# psvsd-v21.net
KiCad netlist of a schematic drawn in EAGLE
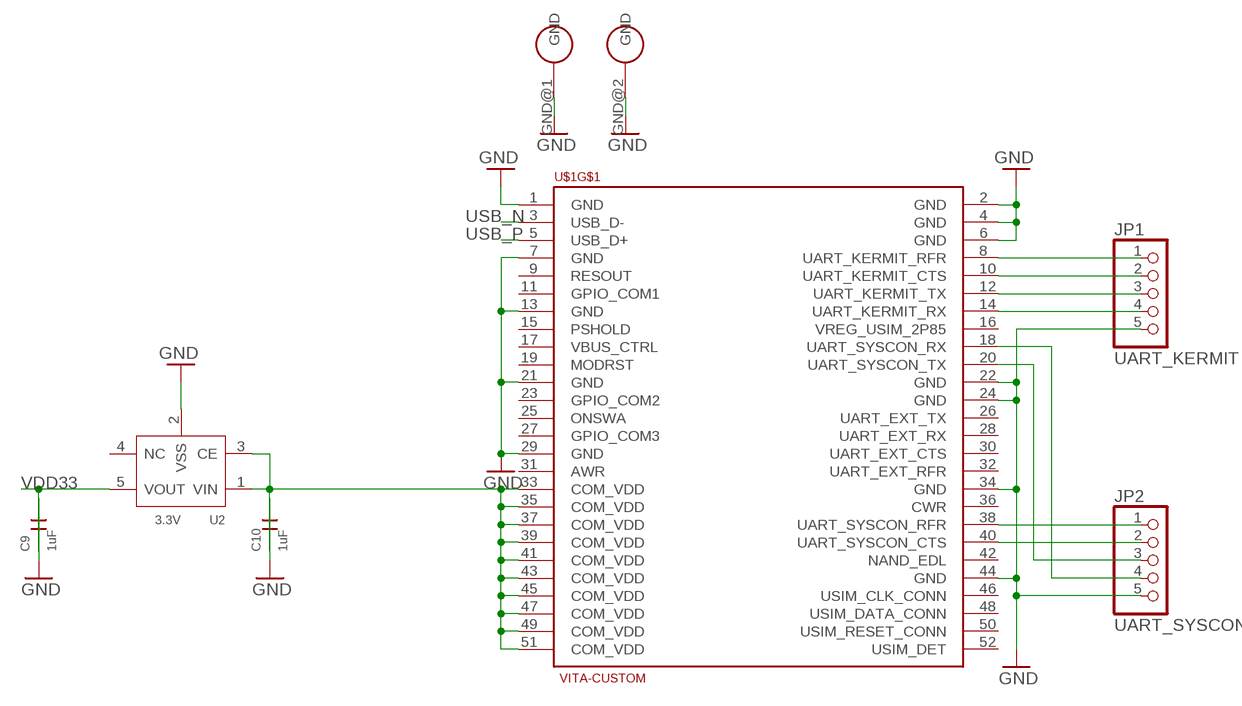
[diagram p0: schematic, sheet 1]
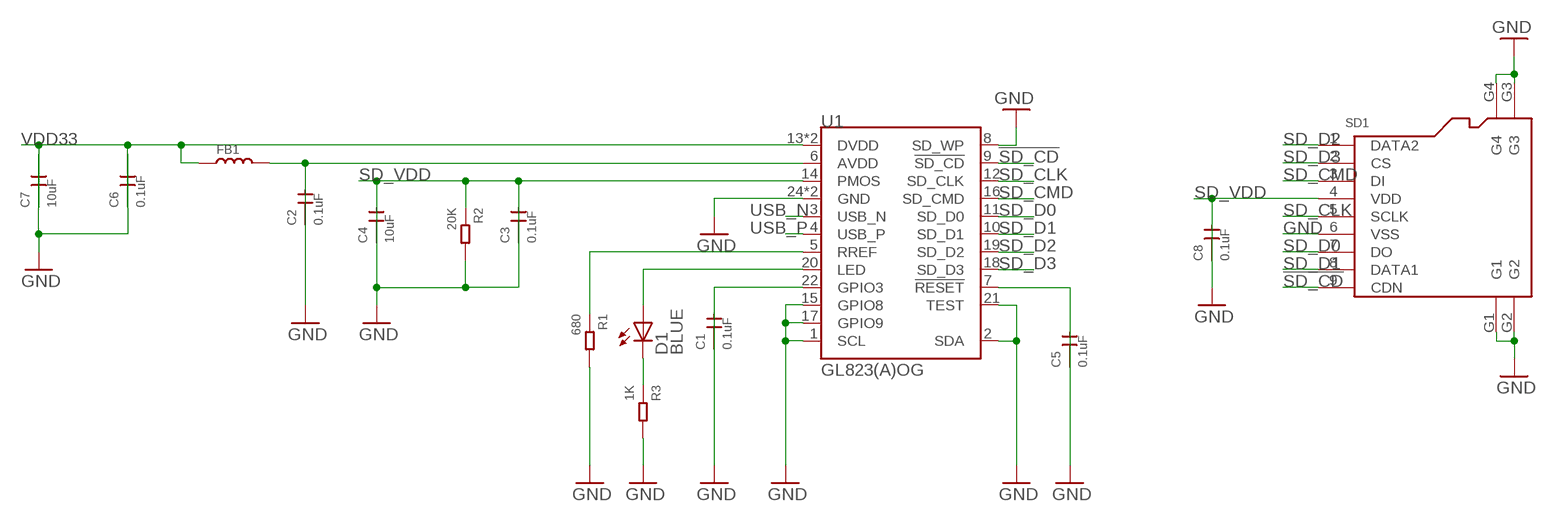
[diagram p1: schematic, sheet 2]

(export (version "E")
  (design (tool "Eeschema 10.0.6"))
  (components
    (comp (ref "C9")
      (value "1uF")
      (footprint "eagle-import:C0603")
      (fields (field (name "MPN") "GRM1885C1H102JA01D"))
      (libsource (lib "eagle-import") (part "CERAMIC-1NF-50V-5%-C0G(0603)"))
    )
    (comp (ref "C10")
      (value "1uF")
      (footprint "eagle-import:C0603")
      (fields (field (name "MPN") "GRM1885C1H102JA01D"))
      (libsource (lib "eagle-import") (part "CERAMIC-1NF-50V-5%-C0G(0603)"))
    )
    (comp (ref "JP1")
      (value "UART_KERMIT")
      (footprint "eagle-import:1X05")
      (libsource (lib "eagle-import") (part "PINHD-1X5"))
    )
    (comp (ref "JP2")
      (value "UART_SYSCON")
      (footprint "eagle-import:1X05")
      (libsource (lib "eagle-import") (part "PINHD-1X5"))
    )
    (comp (ref "U$1")
      (value "VITA-CUSTOM")
      (footprint "eagle-import:VITA-MINI-PCI-E")
      (libsource (lib "eagle-import") (part "VITA-CUSTOM"))
    )
    (comp (ref "U2")
      (value "3.3V")
      (footprint "eagle-import:SOT-23-5")
      (fields (field (name "MPN") "XC6204B332MR"))
      (libsource (lib "eagle-import") (part "PMIC-LDO-XC6204B332MR(SOT23-5)"))
    )
    (comp (ref "C1")
      (value "0.1uF")
      (footprint "eagle-import:C0603")
      (fields (field (name "MPN") "GRM1885C1H102JA01D"))
      (libsource (lib "eagle-import") (part "CERAMIC-1NF-50V-5%-C0G(0603)"))
    )
    (comp (ref "C2")
      (value "0.1uF")
      (footprint "eagle-import:C0603")
      (fields (field (name "MPN") "GRM1885C1H102JA01D"))
      (libsource (lib "eagle-import") (part "CERAMIC-1NF-50V-5%-C0G(0603)"))
    )
    (comp (ref "C3")
      (value "0.1uF")
      (footprint "eagle-import:C0603")
      (fields (field (name "MPN") "GRM1885C1H102JA01D"))
      (libsource (lib "eagle-import") (part "CERAMIC-1NF-50V-5%-C0G(0603)"))
    )
    (comp (ref "C4")
      (value "10uF")
      (footprint "eagle-import:C0603")
      (fields (field (name "MPN") "GRM1885C1H102JA01D"))
      (libsource (lib "eagle-import") (part "CERAMIC-1NF-50V-5%-C0G(0603)"))
    )
    (comp (ref "C5")
      (value "0.1uF")
      (footprint "eagle-import:C0603")
      (fields (field (name "MPN") "GRM1885C1H102JA01D"))
      (libsource (lib "eagle-import") (part "CERAMIC-1NF-50V-5%-C0G(0603)"))
    )
    (comp (ref "C6")
      (value "0.1uF")
      (footprint "eagle-import:C0603")
      (fields (field (name "MPN") "GRM1885C1H102JA01D"))
      (libsource (lib "eagle-import") (part "CERAMIC-1NF-50V-5%-C0G(0603)"))
    )
    (comp (ref "C7")
      (value "10uF")
      (footprint "eagle-import:C0603")
      (fields (field (name "MPN") "GRM1885C1H102JA01D"))
      (libsource (lib "eagle-import") (part "CERAMIC-1NF-50V-5%-C0G(0603)"))
    )
    (comp (ref "C8")
      (value "0.1uF")
      (footprint "eagle-import:C0603")
      (fields (field (name "MPN") "GRM1885C1H102JA01D"))
      (libsource (lib "eagle-import") (part "CERAMIC-1NF-50V-5%-C0G(0603)"))
    )
    (comp (ref "D1")
      (value "BLUE")
      (footprint "eagle-import:CHIP-LED0603")
      (libsource (lib "eagle-import") (part "LEDCHIP-LED0603"))
    )
    (comp (ref "FB1")
      (value "SMD-FERRITE-BEAD-2500R-50MA(0603)")
      (footprint "eagle-import:L0603")
      (libsource (lib "eagle-import") (part "SMD-FERRITE-BEAD-2500R-50MA(0603)"))
    )
    (comp (ref "R1")
      (value "680")
      (footprint "eagle-import:R0603")
      (fields (field (name "MPN") "RC0603JR-070RL"))
      (libsource (lib "eagle-import") (part "SMD-RES-0R-5%-1/10W(0603)"))
    )
    (comp (ref "R2")
      (value "20K")
      (footprint "eagle-import:R0603")
      (fields (field (name "MPN") "RC0603JR-070RL"))
      (libsource (lib "eagle-import") (part "SMD-RES-0R-5%-1/10W(0603)"))
    )
    (comp (ref "R3")
      (value "1K")
      (footprint "eagle-import:R0603")
      (fields (field (name "MPN") "RC0603JR-070RL"))
      (libsource (lib "eagle-import") (part "SMD-RES-0R-5%-1/10W(0603)"))
    )
    (comp (ref "SD1")
      (value "MICRO-SD-CARD-SOCKET-9P(ST-TF-003A)")
      (footprint "eagle-import:MICRO-SD9+4P-SMD-16.1X14.5X1.85MM")
      (fields (field (name "MPN") "ST-TF-003A"))
      (libsource (lib "eagle-import") (part "MICRO-SD-CARD-SOCKET-9P(ST-TF-003A)"))
    )
    (comp (ref "U1")
      (value "GL823(A)OG")
      (footprint "eagle-import:QFN-24")
      (libsource (lib "eagle-import") (part "GL823(A)OG"))
    )
  )
  (nets
    (net (code "1") (name "GND") (class "Default")
      (node (ref "C1") (pin "2") (pinfunction "2_2") (pintype "passive"))
      (node (ref "C10") (pin "2") (pinfunction "2_2") (pintype "passive"))
      (node (ref "C2") (pin "2") (pinfunction "2_2") (pintype "passive"))
      (node (ref "C3") (pin "2") (pinfunction "2_2") (pintype "passive"))
      (node (ref "C4") (pin "2") (pinfunction "2_2") (pintype "passive"))
      (node (ref "C5") (pin "2") (pinfunction "2_2") (pintype "passive"))
      (node (ref "C6") (pin "2") (pinfunction "2_2") (pintype "passive"))
      (node (ref "C7") (pin "2") (pinfunction "2_2") (pintype "passive"))
      (node (ref "C8") (pin "2") (pinfunction "2_2") (pintype "passive"))
      (node (ref "C9") (pin "2") (pinfunction "2_2") (pintype "passive"))
      (node (ref "JP1") (pin "5") (pinfunction "5_5") (pintype "passive"))
      (node (ref "JP2") (pin "5") (pinfunction "5_5") (pintype "passive"))
      (node (ref "R1") (pin "2") (pinfunction "2_2") (pintype "passive"))
      (node (ref "R2") (pin "2") (pinfunction "2_2") (pintype "passive"))
      (node (ref "R3") (pin "2") (pinfunction "2_2") (pintype "passive"))
      (node (ref "SD1") (pin "6") (pinfunction "VSS_6") (pintype "bidirectional"))
      (node (ref "SD1") (pin "G1") (pinfunction "G1_G1") (pintype "bidirectional"))
      (node (ref "SD1") (pin "G2") (pinfunction "G2_G2") (pintype "bidirectional"))
      (node (ref "SD1") (pin "G3") (pinfunction "G3_G3") (pintype "bidirectional"))
      (node (ref "SD1") (pin "G4") (pinfunction "G4_G4") (pintype "bidirectional"))
      (node (ref "U$1") (pin "1") (pinfunction "GND_1") (pintype "bidirectional"))
      (node (ref "U$1") (pin "13") (pinfunction "GND_13") (pintype "bidirectional"))
      (node (ref "U$1") (pin "2") (pinfunction "GND_2") (pintype "bidirectional"))
      (node (ref "U$1") (pin "21") (pinfunction "GND_21") (pintype "bidirectional"))
      (node (ref "U$1") (pin "22") (pinfunction "GND_22") (pintype "bidirectional"))
      (node (ref "U$1") (pin "24") (pinfunction "GND_24") (pintype "bidirectional"))
      (node (ref "U$1") (pin "29") (pinfunction "GND_29") (pintype "bidirectional"))
      (node (ref "U$1") (pin "34") (pinfunction "GND_34") (pintype "bidirectional"))
      (node (ref "U$1") (pin "4") (pinfunction "GND_4") (pintype "bidirectional"))
      (node (ref "U$1") (pin "44") (pinfunction "GND_44") (pintype "bidirectional"))
      (node (ref "U$1") (pin "6") (pinfunction "GND_6") (pintype "bidirectional"))
      (node (ref "U$1") (pin "7") (pinfunction "GND_7") (pintype "bidirectional"))
      (node (ref "U$1") (pin "GND@1") (pinfunction "GND_GND@1") (pintype "power_in"))
      (node (ref "U$1") (pin "GND@2") (pinfunction "GND_GND@2") (pintype "power_in"))
      (node (ref "U1") (pin "1") (pinfunction "SCL_1") (pintype "bidirectional"))
      (node (ref "U1") (pin "15") (pinfunction "GPIO8_15") (pintype "bidirectional"))
      (node (ref "U1") (pin "17") (pinfunction "GPIO9_17") (pintype "bidirectional"))
      (node (ref "U1") (pin "2") (pinfunction "SDA_2") (pintype "bidirectional"))
      (node (ref "U1") (pin "21") (pinfunction "TEST_21") (pintype "input"))
      (node (ref "U1") (pin "24") (pinfunction "GND_24") (pintype "power_in"))
      (node (ref "U1") (pin "25") (pinfunction "GND_25") (pintype "power_in"))
      (node (ref "U1") (pin "8") (pinfunction "SD_WP_8") (pintype "input"))
      (node (ref "U2") (pin "2") (pinfunction "VSS_2") (pintype "power_in"))
    )
    (net (code "2") (name "Net-(D1-PadC)") (class "Default")
      (node (ref "D1") (pin "C") (pinfunction "C_C") (pintype "passive"))
      (node (ref "R3") (pin "1") (pinfunction "1_1") (pintype "passive"))
    )
    (net (code "3") (name "Net-(U$1A-UART_KERMIT_CTS)") (class "Default")
      (node (ref "JP1") (pin "2") (pinfunction "2_2") (pintype "passive"))
      (node (ref "U$1") (pin "10") (pinfunction "UART_KERMIT_CTS_10") (pintype "bidirectional"))
    )
    (net (code "4") (name "Net-(U$1A-UART_KERMIT_RFR)") (class "Default")
      (node (ref "JP1") (pin "1") (pinfunction "1_1") (pintype "passive"))
      (node (ref "U$1") (pin "8") (pinfunction "UART_KERMIT_RFR_8") (pintype "bidirectional"))
    )
    (net (code "5") (name "Net-(U$1A-UART_KERMIT_RX)") (class "Default")
      (node (ref "JP1") (pin "4") (pinfunction "4_4") (pintype "passive"))
      (node (ref "U$1") (pin "14") (pinfunction "UART_KERMIT_RX_14") (pintype "bidirectional"))
    )
    (net (code "6") (name "Net-(U$1A-UART_KERMIT_TX)") (class "Default")
      (node (ref "JP1") (pin "3") (pinfunction "3_3") (pintype "passive"))
      (node (ref "U$1") (pin "12") (pinfunction "UART_KERMIT_TX_12") (pintype "bidirectional"))
    )
    (net (code "7") (name "Net-(U$1A-UART_SYSCON_CTS)") (class "Default")
      (node (ref "JP2") (pin "2") (pinfunction "2_2") (pintype "passive"))
      (node (ref "U$1") (pin "40") (pinfunction "UART_SYSCON_CTS_40") (pintype "bidirectional"))
    )
    (net (code "8") (name "Net-(U$1A-UART_SYSCON_RFR)") (class "Default")
      (node (ref "JP2") (pin "1") (pinfunction "1_1") (pintype "passive"))
      (node (ref "U$1") (pin "38") (pinfunction "UART_SYSCON_RFR_38") (pintype "bidirectional"))
    )
    (net (code "9") (name "Net-(U$1A-UART_SYSCON_RX)") (class "Default")
      (node (ref "JP2") (pin "4") (pinfunction "4_4") (pintype "passive"))
      (node (ref "U$1") (pin "18") (pinfunction "UART_SYSCON_RX_18") (pintype "bidirectional"))
    )
    (net (code "10") (name "Net-(U$1A-UART_SYSCON_TX)") (class "Default")
      (node (ref "JP2") (pin "3") (pinfunction "3_3") (pintype "passive"))
      (node (ref "U$1") (pin "20") (pinfunction "UART_SYSCON_TX_20") (pintype "bidirectional"))
    )
    (net (code "11") (name "Net-(U1-AVDD)") (class "Default")
      (node (ref "C2") (pin "1") (pinfunction "1_1") (pintype "passive"))
      (node (ref "FB1") (pin "2") (pinfunction "2_2") (pintype "passive"))
      (node (ref "U1") (pin "6") (pinfunction "AVDD_6") (pintype "power_in"))
    )
    (net (code "12") (name "Net-(U1-GPIO3)") (class "Default")
      (node (ref "C1") (pin "1") (pinfunction "1_1") (pintype "passive"))
      (node (ref "U1") (pin "22") (pinfunction "GPIO3_22") (pintype "bidirectional"))
    )
    (net (code "13") (name "Net-(U1-LED)") (class "Default")
      (node (ref "D1") (pin "A") (pinfunction "A_A") (pintype "passive"))
      (node (ref "U1") (pin "20") (pinfunction "LED_20") (pintype "output"))
    )
    (net (code "14") (name "Net-(U1-RREF)") (class "Default")
      (node (ref "R1") (pin "1") (pinfunction "1_1") (pintype "passive"))
      (node (ref "U1") (pin "5") (pinfunction "RREF_5") (pintype "bidirectional"))
    )
    (net (code "15") (name "Net-(U1-~{RESET})") (class "Default")
      (node (ref "C5") (pin "1") (pinfunction "1_1") (pintype "passive"))
      (node (ref "U1") (pin "7") (pinfunction "~{RESET}_7") (pintype "input"))
    )
    (net (code "16") (name "Net-(U2-CE)") (class "Default")
      (node (ref "C10") (pin "1") (pinfunction "1_1") (pintype "passive"))
      (node (ref "U$1") (pin "33") (pinfunction "COM_VDD_33") (pintype "bidirectional"))
      (node (ref "U$1") (pin "35") (pinfunction "COM_VDD_35") (pintype "bidirectional"))
      (node (ref "U$1") (pin "37") (pinfunction "COM_VDD_37") (pintype "bidirectional"))
      (node (ref "U$1") (pin "39") (pinfunction "COM_VDD_39") (pintype "bidirectional"))
      (node (ref "U$1") (pin "41") (pinfunction "COM_VDD_41") (pintype "bidirectional"))
      (node (ref "U$1") (pin "43") (pinfunction "COM_VDD_43") (pintype "bidirectional"))
      (node (ref "U$1") (pin "45") (pinfunction "COM_VDD_45") (pintype "bidirectional"))
      (node (ref "U$1") (pin "47") (pinfunction "COM_VDD_47") (pintype "bidirectional"))
      (node (ref "U$1") (pin "49") (pinfunction "COM_VDD_49") (pintype "bidirectional"))
      (node (ref "U$1") (pin "51") (pinfunction "COM_VDD_51") (pintype "bidirectional"))
      (node (ref "U2") (pin "1") (pinfunction "VIN_1") (pintype "input"))
      (node (ref "U2") (pin "3") (pinfunction "CE_3") (pintype "bidirectional"))
    )
    (net (code "17") (name "SD_CLK") (class "Default")
      (node (ref "SD1") (pin "5") (pinfunction "SCLK_5") (pintype "bidirectional"))
      (node (ref "U1") (pin "12") (pinfunction "SD_CLK_12") (pintype "output"))
    )
    (net (code "18") (name "SD_CMD") (class "Default")
      (node (ref "SD1") (pin "3") (pinfunction "DI_3") (pintype "bidirectional"))
      (node (ref "U1") (pin "16") (pinfunction "SD_CMD_16") (pintype "bidirectional"))
    )
    (net (code "19") (name "SD_D0") (class "Default")
      (node (ref "SD1") (pin "7") (pinfunction "DO_7") (pintype "bidirectional"))
      (node (ref "U1") (pin "11") (pinfunction "SD_D0_11") (pintype "bidirectional"))
    )
    (net (code "20") (name "SD_D1") (class "Default")
      (node (ref "SD1") (pin "8") (pinfunction "DATA1_8") (pintype "bidirectional"))
      (node (ref "U1") (pin "10") (pinfunction "SD_D1_10") (pintype "bidirectional"))
    )
    (net (code "21") (name "SD_D2") (class "Default")
      (node (ref "SD1") (pin "1") (pinfunction "DATA2_1") (pintype "bidirectional"))
      (node (ref "U1") (pin "19") (pinfunction "SD_D2_19") (pintype "bidirectional"))
    )
    (net (code "22") (name "SD_D3") (class "Default")
      (node (ref "SD1") (pin "2") (pinfunction "CS_2") (pintype "bidirectional"))
      (node (ref "U1") (pin "18") (pinfunction "SD_D3_18") (pintype "bidirectional"))
    )
    (net (code "23") (name "SD_VDD") (class "Default")
      (node (ref "C3") (pin "1") (pinfunction "1_1") (pintype "passive"))
      (node (ref "C4") (pin "1") (pinfunction "1_1") (pintype "passive"))
      (node (ref "C8") (pin "1") (pinfunction "1_1") (pintype "passive"))
      (node (ref "R2") (pin "1") (pinfunction "1_1") (pintype "passive"))
      (node (ref "SD1") (pin "4") (pinfunction "VDD_4") (pintype "bidirectional"))
      (node (ref "U1") (pin "14") (pinfunction "PMOS_14") (pintype "power_in"))
    )
    (net (code "24") (name "USB_N") (class "Default")
      (node (ref "U$1") (pin "3") (pinfunction "USB_D-_3") (pintype "bidirectional"))
      (node (ref "U1") (pin "3") (pinfunction "USB_N_3") (pintype "bidirectional"))
    )
    (net (code "25") (name "USB_P") (class "Default")
      (node (ref "U$1") (pin "5") (pinfunction "USB_D+_5") (pintype "bidirectional"))
      (node (ref "U1") (pin "4") (pinfunction "USB_P_4") (pintype "bidirectional"))
    )
    (net (code "26") (name "VDD33") (class "Default")
      (node (ref "C6") (pin "1") (pinfunction "1_1") (pintype "passive"))
      (node (ref "C7") (pin "1") (pinfunction "1_1") (pintype "passive"))
      (node (ref "C9") (pin "1") (pinfunction "1_1") (pintype "passive"))
      (node (ref "FB1") (pin "1") (pinfunction "1_1") (pintype "passive"))
      (node (ref "U1") (pin "13") (pinfunction "DVDD_13") (pintype "power_in"))
      (node (ref "U1") (pin "23") (pinfunction "DVDD_23") (pintype "power_in"))
      (node (ref "U2") (pin "5") (pinfunction "VOUT_5") (pintype "output"))
    )
    (net (code "27") (name "unconnected-(U$1A-AWR-Pad31)") (class "Default")
      (node (ref "U$1") (pin "31") (pinfunction "AWR_31") (pintype "bidirectional"))
    )
    (net (code "28") (name "unconnected-(U$1A-CWR-Pad36)") (class "Default")
      (node (ref "U$1") (pin "36") (pinfunction "CWR_36") (pintype "bidirectional"))
    )
    (net (code "29") (name "unconnected-(U$1A-GPIO_COM1-Pad11)") (class "Default")
      (node (ref "U$1") (pin "11") (pinfunction "GPIO_COM1_11") (pintype "bidirectional"))
    )
    (net (code "30") (name "unconnected-(U$1A-GPIO_COM2-Pad23)") (class "Default")
      (node (ref "U$1") (pin "23") (pinfunction "GPIO_COM2_23") (pintype "bidirectional"))
    )
    (net (code "31") (name "unconnected-(U$1A-GPIO_COM3-Pad27)") (class "Default")
      (node (ref "U$1") (pin "27") (pinfunction "GPIO_COM3_27") (pintype "bidirectional"))
    )
    (net (code "32") (name "unconnected-(U$1A-MODRST-Pad19)") (class "Default")
      (node (ref "U$1") (pin "19") (pinfunction "MODRST_19") (pintype "bidirectional"))
    )
    (net (code "33") (name "unconnected-(U$1A-NAND_EDL-Pad42)") (class "Default")
      (node (ref "U$1") (pin "42") (pinfunction "NAND_EDL_42") (pintype "bidirectional"))
    )
    (net (code "34") (name "unconnected-(U$1A-ONSWA-Pad25)") (class "Default")
      (node (ref "U$1") (pin "25") (pinfunction "ONSWA_25") (pintype "bidirectional"))
    )
    (net (code "35") (name "unconnected-(U$1A-PSHOLD-Pad15)") (class "Default")
      (node (ref "U$1") (pin "15") (pinfunction "PSHOLD_15") (pintype "bidirectional"))
    )
    (net (code "36") (name "unconnected-(U$1A-RESOUT-Pad9)") (class "Default")
      (node (ref "U$1") (pin "9") (pinfunction "RESOUT_9") (pintype "bidirectional"))
    )
    (net (code "37") (name "unconnected-(U$1A-UART_EXT_CTS-Pad30)") (class "Default")
      (node (ref "U$1") (pin "30") (pinfunction "UART_EXT_CTS_30") (pintype "bidirectional"))
    )
    (net (code "38") (name "unconnected-(U$1A-UART_EXT_RFR-Pad32)") (class "Default")
      (node (ref "U$1") (pin "32") (pinfunction "UART_EXT_RFR_32") (pintype "bidirectional"))
    )
    (net (code "39") (name "unconnected-(U$1A-UART_EXT_RX-Pad28)") (class "Default")
      (node (ref "U$1") (pin "28") (pinfunction "UART_EXT_RX_28") (pintype "bidirectional"))
    )
    (net (code "40") (name "unconnected-(U$1A-UART_EXT_TX-Pad26)") (class "Default")
      (node (ref "U$1") (pin "26") (pinfunction "UART_EXT_TX_26") (pintype "bidirectional"))
    )
    (net (code "41") (name "unconnected-(U$1A-USIM_CLK_CONN-Pad46)") (class "Default")
      (node (ref "U$1") (pin "46") (pinfunction "USIM_CLK_CONN_46") (pintype "bidirectional"))
    )
    (net (code "42") (name "unconnected-(U$1A-USIM_DATA_CONN-Pad48)") (class "Default")
      (node (ref "U$1") (pin "48") (pinfunction "USIM_DATA_CONN_48") (pintype "bidirectional"))
    )
    (net (code "43") (name "unconnected-(U$1A-USIM_DET-Pad52)") (class "Default")
      (node (ref "U$1") (pin "52") (pinfunction "USIM_DET_52") (pintype "bidirectional"))
    )
    (net (code "44") (name "unconnected-(U$1A-USIM_RESET_CONN-Pad50)") (class "Default")
      (node (ref "U$1") (pin "50") (pinfunction "USIM_RESET_CONN_50") (pintype "bidirectional"))
    )
    (net (code "45") (name "unconnected-(U$1A-VBUS_CTRL-Pad17)") (class "Default")
      (node (ref "U$1") (pin "17") (pinfunction "VBUS_CTRL_17") (pintype "bidirectional"))
    )
    (net (code "46") (name "unconnected-(U$1A-VREG_USIM_2P85-Pad16)") (class "Default")
      (node (ref "U$1") (pin "16") (pinfunction "VREG_USIM_2P85_16") (pintype "bidirectional"))
    )
    (net (code "47") (name "unconnected-(U2-NC-Pad4)") (class "Default")
      (node (ref "U2") (pin "4") (pinfunction "NC_4") (pintype "no_connect"))
    )
    (net (code "48") (name "~{SD_CD}") (class "Default")
      (node (ref "SD1") (pin "9") (pinfunction "CDN_9") (pintype "bidirectional"))
      (node (ref "U1") (pin "9") (pinfunction "~{SD_CD}_9") (pintype "input"))
    )
  )
)
